# Sheet1.net
KiCad netlist of a schematic drawn in Altium Designer
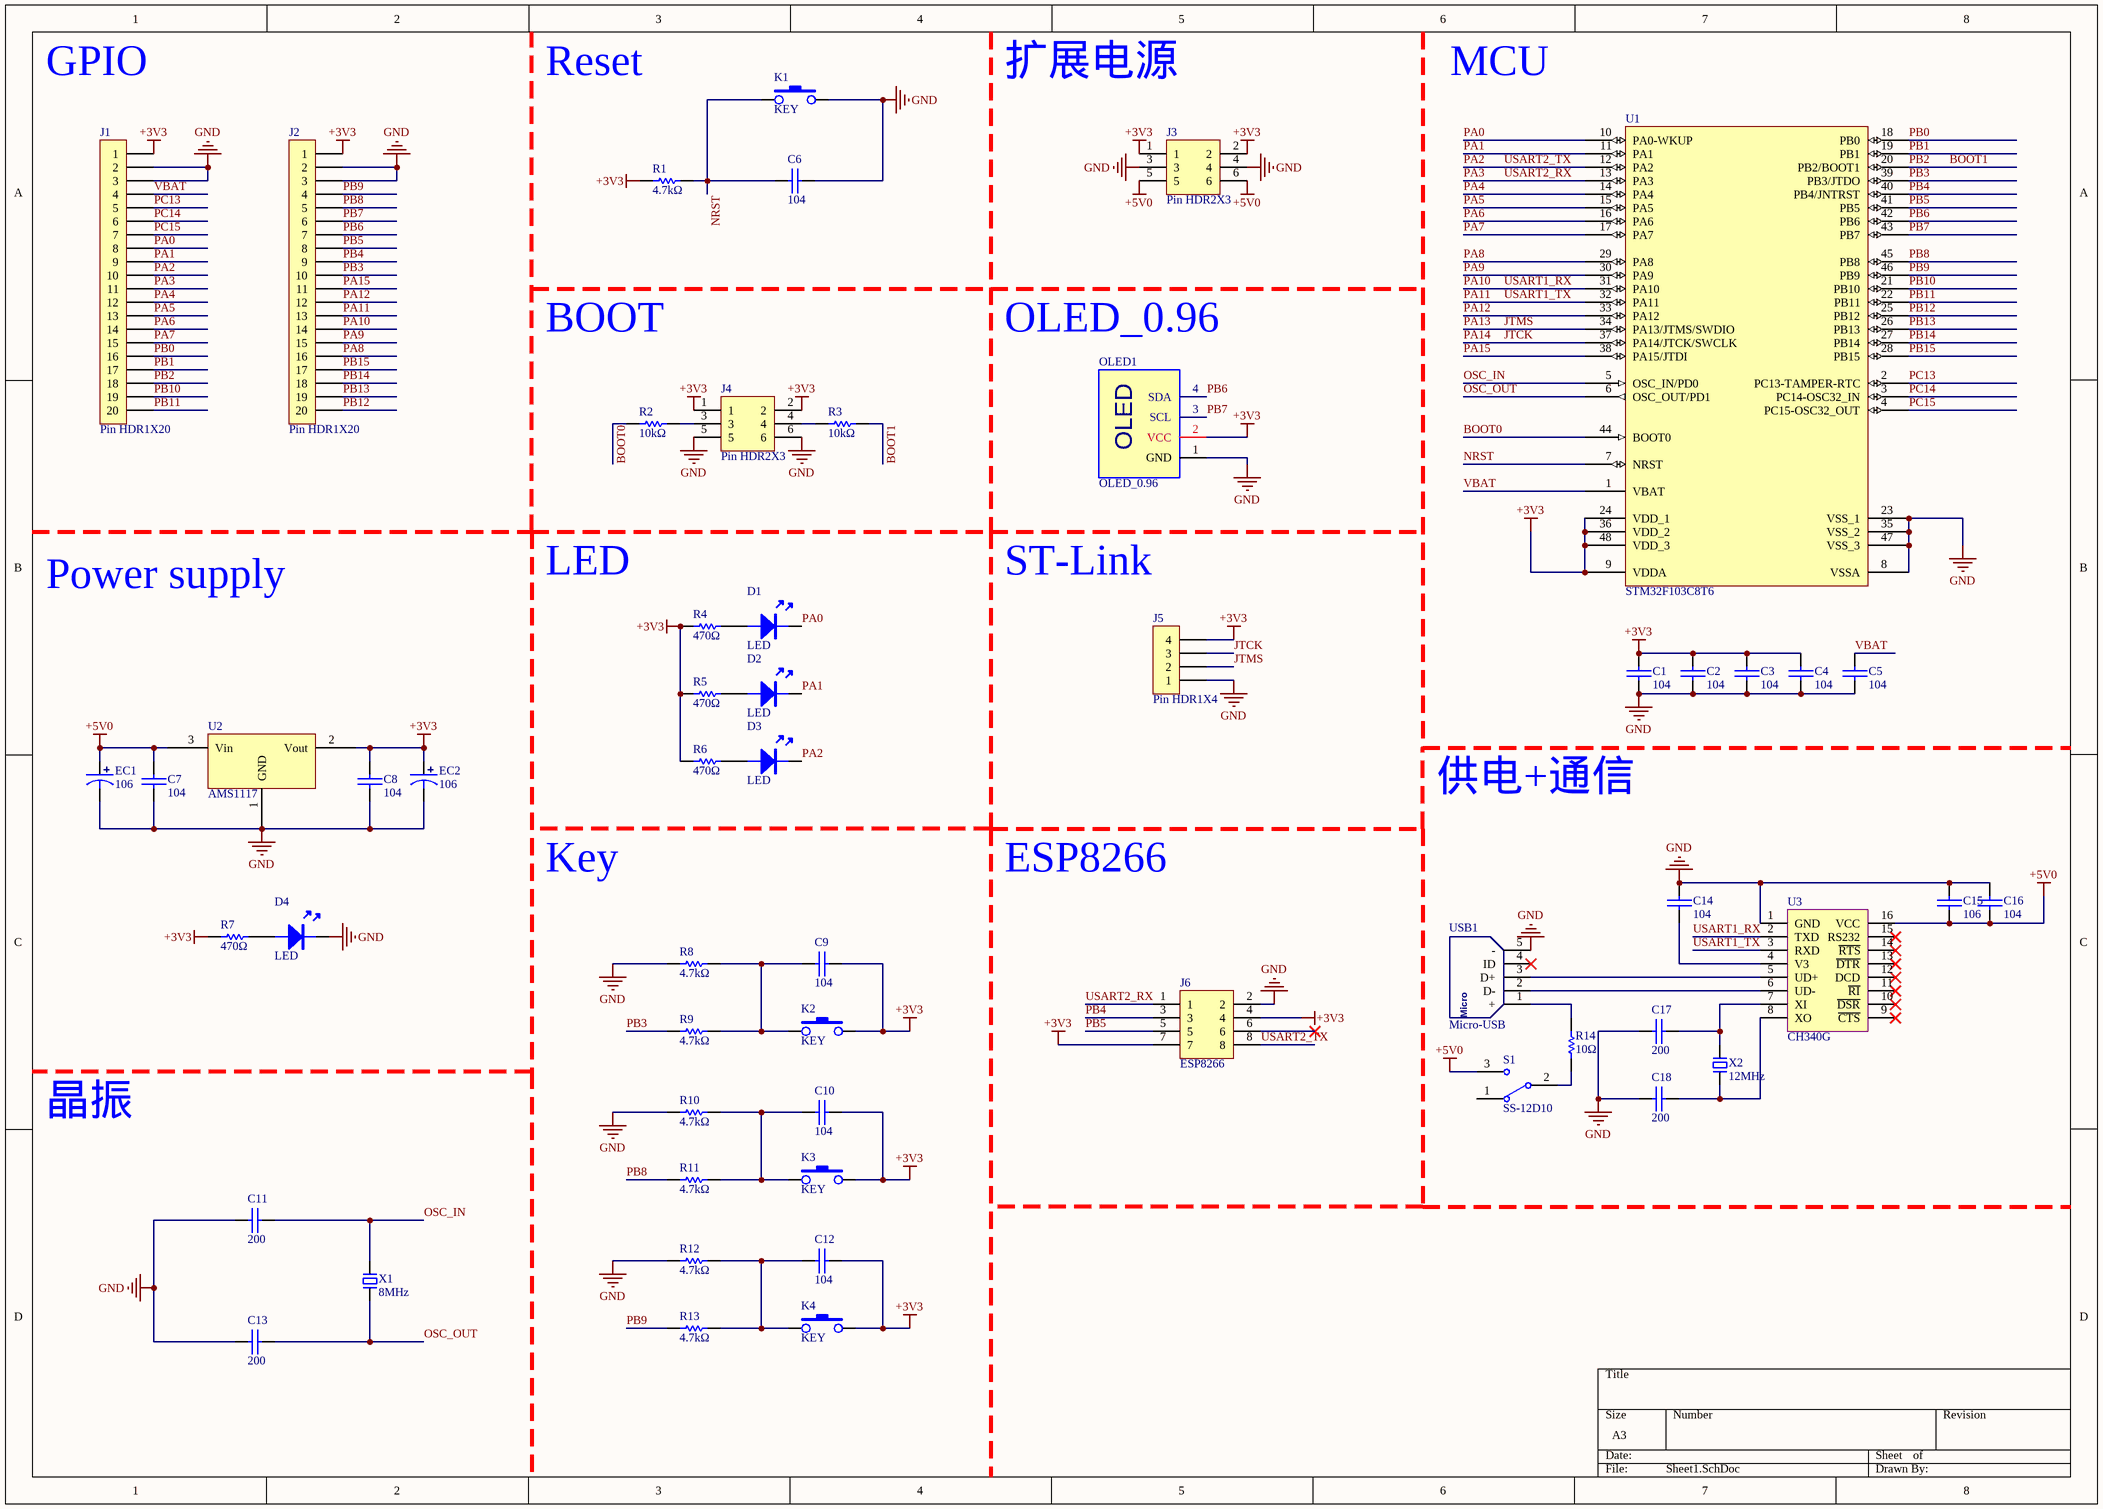
[diagram p0: Sheet1.SchDoc]

(export (version "E")
  (design (tool "Eeschema 10.0.6"))
  (components
    (comp (ref "C1")
      (value "104")
      (footprint "0805C")
      (description "无极性电容")
      (libsource (lib "电容") (part "CAP"))
    )
    (comp (ref "C2")
      (value "104")
      (footprint "0805C")
      (description "无极性电容")
      (libsource (lib "电容") (part "CAP"))
    )
    (comp (ref "C3")
      (value "104")
      (footprint "0805C")
      (description "无极性电容")
      (libsource (lib "电容") (part "CAP"))
    )
    (comp (ref "C4")
      (value "104")
      (footprint "0805C")
      (description "无极性电容")
      (libsource (lib "电容") (part "CAP"))
    )
    (comp (ref "C5")
      (value "104")
      (footprint "0805C")
      (description "无极性电容")
      (libsource (lib "电容") (part "CAP"))
    )
    (comp (ref "C6")
      (value "104")
      (footprint "0805C")
      (description "无极性电容")
      (libsource (lib "电容") (part "CAP"))
    )
    (comp (ref "C7")
      (value "104")
      (footprint "0805C")
      (description "无极性电容")
      (libsource (lib "电容") (part "CAP"))
    )
    (comp (ref "C8")
      (value "104")
      (footprint "0805C")
      (description "无极性电容")
      (libsource (lib "电容") (part "CAP"))
    )
    (comp (ref "C9")
      (value "104")
      (footprint "0805C")
      (description "无极性电容")
      (libsource (lib "电容") (part "CAP"))
    )
    (comp (ref "C10")
      (value "104")
      (footprint "0805C")
      (description "无极性电容")
      (libsource (lib "电容") (part "CAP"))
    )
    (comp (ref "C11")
      (value "200")
      (footprint "0805C")
      (description "无极性电容")
      (libsource (lib "电容") (part "CAP"))
    )
    (comp (ref "C12")
      (value "104")
      (footprint "0805C")
      (description "无极性电容")
      (libsource (lib "电容") (part "CAP"))
    )
    (comp (ref "C13")
      (value "200")
      (footprint "0805C")
      (description "无极性电容")
      (libsource (lib "电容") (part "CAP"))
    )
    (comp (ref "C14")
      (value "104")
      (footprint "0805C")
      (description "无极性电容")
      (libsource (lib "电容") (part "CAP"))
    )
    (comp (ref "C15")
      (value "106")
      (footprint "0805C")
      (description "无极性电容")
      (libsource (lib "电容") (part "CAP"))
    )
    (comp (ref "C16")
      (value "104")
      (footprint "0805C")
      (description "无极性电容")
      (libsource (lib "电容") (part "CAP"))
    )
    (comp (ref "C17")
      (value "200")
      (footprint "0805C")
      (description "无极性电容")
      (libsource (lib "电容") (part "CAP"))
    )
    (comp (ref "C18")
      (value "200")
      (footprint "0805C")
      (description "无极性电容")
      (libsource (lib "电容") (part "CAP"))
    )
    (comp (ref "D1") (value "LED") (footprint "LED-0805R") (libsource (lib "LED") (part "LED")))
    (comp (ref "D2") (value "LED") (footprint "LED-0805G") (libsource (lib "LED") (part "LED")))
    (comp (ref "D3") (value "LED") (footprint "LED-0805B") (libsource (lib "LED") (part "LED")))
    (comp (ref "D4") (value "LED") (footprint "LED-0805B") (libsource (lib "LED") (part "LED")))
    (comp (ref "EC1")
      (value "106")
      (footprint "SMD-EC4.0X4.3X5.4")
      (description "贴片电解电容")
      (libsource (lib "电容") (part "SMD_ECAP"))
    )
    (comp (ref "EC2")
      (value "106")
      (footprint "SMD-EC4.0X4.3X5.4")
      (description "贴片电解电容")
      (libsource (lib "电容") (part "SMD_ECAP"))
    )
    (comp (ref "J1")
      (value "Pin HDR1X20")
      (footprint "Pin HDR1X20/2.54mm-S")
      (libsource (lib "排针") (part "Pin HDR1X20"))
    )
    (comp (ref "J2")
      (value "Pin HDR1X20")
      (footprint "Pin HDR1X20/2.54mm-S")
      (libsource (lib "排针") (part "Pin HDR1X20"))
    )
    (comp (ref "J3")
      (value "Pin HDR2X3")
      (footprint "Pin HDR2X3/2.54mm-S")
      (libsource (lib "排针") (part "Pin HDR2X3"))
    )
    (comp (ref "J4")
      (value "Pin HDR2X3")
      (footprint "Pin HDR2X3/2.54mm-S")
      (libsource (lib "排针") (part "Pin HDR2X3"))
    )
    (comp (ref "J5")
      (value "Pin HDR1X4")
      (footprint "Pin HDR1X4/2.54mm-S")
      (libsource (lib "排针") (part "Pin HDR1X4"))
    )
    (comp (ref "J6")
      (value "ESP8266")
      (footprint "Fe-HDR2X4/2.54-S")
      (libsource (lib "排母") (part "Female HDR2X4"))
    )
    (comp (ref "K1") (value "KEY") (footprint "SMD-6X6X5") (libsource (lib "轻触开关") (part "KEY")))
    (comp (ref "K2") (value "KEY") (footprint "SMD-6X6X5") (libsource (lib "轻触开关") (part "KEY")))
    (comp (ref "K3") (value "KEY") (footprint "SMD-6X6X5") (libsource (lib "轻触开关") (part "KEY")))
    (comp (ref "K4") (value "KEY") (footprint "SMD-6X6X5") (libsource (lib "轻触开关") (part "KEY")))
    (comp (ref "OLED1")
      (value "OLED_0.96")
      (footprint "OLED_0.96")
      (libsource (lib "LCD") (part "OLED_0.96"))
    )
    (comp (ref "R1") (value "4.7kΩ") (footprint "0805R") (libsource (lib "电阻") (part "RES")))
    (comp (ref "R2") (value "10kΩ") (footprint "0805R") (libsource (lib "电阻") (part "RES")))
    (comp (ref "R3") (value "10kΩ") (footprint "0805R") (libsource (lib "电阻") (part "RES")))
    (comp (ref "R4") (value "470Ω") (footprint "0805R") (libsource (lib "电阻") (part "RES")))
    (comp (ref "R5") (value "470Ω") (footprint "0805R") (libsource (lib "电阻") (part "RES")))
    (comp (ref "R6") (value "470Ω") (footprint "0805R") (libsource (lib "电阻") (part "RES")))
    (comp (ref "R7") (value "470Ω") (footprint "0805R") (libsource (lib "电阻") (part "RES")))
    (comp (ref "R8") (value "4.7kΩ") (footprint "0805R") (libsource (lib "电阻") (part "RES")))
    (comp (ref "R9") (value "4.7kΩ") (footprint "0805R") (libsource (lib "电阻") (part "RES")))
    (comp (ref "R10") (value "4.7kΩ") (footprint "0805R") (libsource (lib "电阻") (part "RES")))
    (comp (ref "R11") (value "4.7kΩ") (footprint "0805R") (libsource (lib "电阻") (part "RES")))
    (comp (ref "R12") (value "4.7kΩ") (footprint "0805R") (libsource (lib "电阻") (part "RES")))
    (comp (ref "R13") (value "4.7kΩ") (footprint "0805R") (libsource (lib "电阻") (part "RES")))
    (comp (ref "R14") (value "10Ω") (footprint "2512R") (libsource (lib "电阻") (part "RES")))
    (comp (ref "S1") (value "SS-12D10") (footprint "SS-12D10") (libsource (lib "电源开关") (part "SS-12D10")))
    (comp (ref "U1")
      (value "STM32F103C8T6")
      (footprint "LQFP48 7X7")
      (libsource (lib "STM32系列") (part "STM32F103C8T6"))
    )
    (comp (ref "U2")
      (value "AMS1117")
      (footprint "SOT223")
      (description "三端稳压芯片")
      (libsource (lib "电源芯片") (part "AMS1117"))
    )
    (comp (ref "U3") (value "CH340G") (footprint "SOP16") (libsource (lib "通讯系列IC") (part "CH340G")))
    (comp (ref "USB1")
      (value "Micro-USB")
      (footprint "USB-MICRO_A")
      (libsource (lib "USB") (part "Micro-USB"))
    )
    (comp (ref "X1")
      (value "8MHz")
      (footprint "OSC HC-49SMD")
      (description "2脚无源脚晶振")
      (libsource (lib "晶振") (part "XTAL-2P"))
    )
    (comp (ref "X2")
      (value "12MHz")
      (footprint "OSC HC-49SMD")
      (description "2脚无源脚晶振")
      (libsource (lib "晶振") (part "XTAL-2P"))
    )
  )
  (nets
    (net (code "1") (name "+3V3") (class "Default")
      (node (ref "C1") (pin "2") (pinfunction "2_2") (pintype "passive"))
      (node (ref "C10") (pin "2") (pinfunction "2_2") (pintype "passive"))
      (node (ref "C12") (pin "2") (pinfunction "2_2") (pintype "passive"))
      (node (ref "C2") (pin "2") (pinfunction "2_2") (pintype "passive"))
      (node (ref "C3") (pin "2") (pinfunction "2_2") (pintype "passive"))
      (node (ref "C4") (pin "2") (pinfunction "2_2") (pintype "passive"))
      (node (ref "C8") (pin "2") (pinfunction "2_2") (pintype "passive"))
      (node (ref "C9") (pin "2") (pinfunction "2_2") (pintype "passive"))
      (node (ref "EC2") (pin "1") (pinfunction "1_1") (pintype "passive"))
      (node (ref "J1") (pin "1") (pinfunction "1_1") (pintype "passive"))
      (node (ref "J2") (pin "1") (pinfunction "1_1") (pintype "passive"))
      (node (ref "J3") (pin "1") (pinfunction "1_1") (pintype "passive"))
      (node (ref "J3") (pin "2") (pinfunction "2_2") (pintype "passive"))
      (node (ref "J4") (pin "1") (pinfunction "1_1") (pintype "passive"))
      (node (ref "J4") (pin "2") (pinfunction "2_2") (pintype "passive"))
      (node (ref "J5") (pin "4") (pinfunction "4_4") (pintype "passive"))
      (node (ref "J6") (pin "4") (pinfunction "4_4") (pintype "passive"))
      (node (ref "J6") (pin "7") (pinfunction "7_7") (pintype "passive"))
      (node (ref "K2") (pin "3") (pinfunction "3_3") (pintype "passive"))
      (node (ref "K3") (pin "3") (pinfunction "3_3") (pintype "passive"))
      (node (ref "K4") (pin "3") (pinfunction "3_3") (pintype "passive"))
      (node (ref "OLED1") (pin "2") (pinfunction "VCC_2") (pintype "passive"))
      (node (ref "R1") (pin "1") (pinfunction "1_1") (pintype "passive"))
      (node (ref "R4") (pin "1") (pinfunction "1_1") (pintype "passive"))
      (node (ref "R5") (pin "1") (pinfunction "1_1") (pintype "passive"))
      (node (ref "R6") (pin "1") (pinfunction "1_1") (pintype "passive"))
      (node (ref "R7") (pin "1") (pinfunction "1_1") (pintype "passive"))
      (node (ref "U1") (pin "24") (pinfunction "VDD_1_24") (pintype "power_in"))
      (node (ref "U1") (pin "36") (pinfunction "VDD_2_36") (pintype "power_in"))
      (node (ref "U1") (pin "48") (pinfunction "VDD_3_48") (pintype "power_in"))
      (node (ref "U1") (pin "9") (pinfunction "VDDA_9") (pintype "power_in"))
      (node (ref "U2") (pin "2") (pinfunction "Vout_2") (pintype "passive"))
    )
    (net (code "2") (name "+5V0") (class "Default")
      (node (ref "C15") (pin "1") (pinfunction "1_1") (pintype "passive"))
      (node (ref "C16") (pin "1") (pinfunction "1_1") (pintype "passive"))
      (node (ref "C7") (pin "1") (pinfunction "1_1") (pintype "passive"))
      (node (ref "EC1") (pin "1") (pinfunction "1_1") (pintype "passive"))
      (node (ref "J3") (pin "5") (pinfunction "5_5") (pintype "passive"))
      (node (ref "J3") (pin "6") (pinfunction "6_6") (pintype "passive"))
      (node (ref "S1") (pin "3") (pinfunction "3_3") (pintype "passive"))
      (node (ref "U2") (pin "3") (pinfunction "Vin_3") (pintype "passive"))
      (node (ref "U3") (pin "16") (pinfunction "VCC_16") (pintype "passive"))
    )
    (net (code "3") (name "/BOOT0") (class "Default")
      (node (ref "R2") (pin "1") (pinfunction "1_1") (pintype "passive"))
      (node (ref "U1") (pin "44") (pinfunction "BOOT0_44") (pintype "input"))
    )
    (net (code "4") (name "/BOOT1") (class "Default")
      (node (ref "J1") (pin "18") (pinfunction "18_18") (pintype "passive"))
      (node (ref "R3") (pin "2") (pinfunction "2_2") (pintype "passive"))
      (node (ref "U1") (pin "20") (pinfunction "PB2/BOOT1_20") (pintype "bidirectional"))
    )
    (net (code "5") (name "/JTCK") (class "Default")
      (node (ref "J5") (pin "3") (pinfunction "3_3") (pintype "passive"))
      (node (ref "U1") (pin "37") (pinfunction "PA14/JTCK/SWCLK_37") (pintype "bidirectional"))
    )
    (net (code "6") (name "/JTMS") (class "Default")
      (node (ref "J5") (pin "2") (pinfunction "2_2") (pintype "passive"))
      (node (ref "U1") (pin "34") (pinfunction "PA13/JTMS/SWDIO_34") (pintype "bidirectional"))
    )
    (net (code "7") (name "/NRST") (class "Default")
      (node (ref "C6") (pin "1") (pinfunction "1_1") (pintype "passive"))
      (node (ref "K1") (pin "1") (pinfunction "1_1") (pintype "passive"))
      (node (ref "R1") (pin "2") (pinfunction "2_2") (pintype "passive"))
      (node (ref "U1") (pin "7") (pinfunction "NRST_7") (pintype "bidirectional"))
    )
    (net (code "8") (name "/OSC_IN") (class "Default")
      (node (ref "C11") (pin "2") (pinfunction "2_2") (pintype "passive"))
      (node (ref "U1") (pin "5") (pinfunction "OSC_IN/PD0_5") (pintype "input"))
      (node (ref "X1") (pin "2") (pinfunction "2_2") (pintype "passive"))
    )
    (net (code "9") (name "/OSC_OUT") (class "Default")
      (node (ref "C13") (pin "2") (pinfunction "2_2") (pintype "passive"))
      (node (ref "U1") (pin "6") (pinfunction "OSC_OUT/PD1_6") (pintype "output"))
      (node (ref "X1") (pin "1") (pinfunction "1_1") (pintype "passive"))
    )
    (net (code "10") (name "/PA0") (class "Default")
      (node (ref "D1") (pin "K") (pinfunction "K_K") (pintype "passive"))
      (node (ref "J1") (pin "8") (pinfunction "8_8") (pintype "passive"))
      (node (ref "U1") (pin "10") (pinfunction "PA0-WKUP_10") (pintype "bidirectional"))
    )
    (net (code "11") (name "/PA1") (class "Default")
      (node (ref "D2") (pin "K") (pinfunction "K_K") (pintype "passive"))
      (node (ref "J1") (pin "9") (pinfunction "9_9") (pintype "passive"))
      (node (ref "U1") (pin "11") (pinfunction "PA1_11") (pintype "bidirectional"))
    )
    (net (code "12") (name "/PA2") (class "Default")
      (node (ref "D3") (pin "K") (pinfunction "K_K") (pintype "passive"))
      (node (ref "J1") (pin "10") (pinfunction "10_10") (pintype "passive"))
      (node (ref "J6") (pin "8") (pinfunction "8_8") (pintype "passive"))
      (node (ref "U1") (pin "12") (pinfunction "PA2_12") (pintype "bidirectional"))
    )
    (net (code "13") (name "/PA3") (class "Default")
      (node (ref "J1") (pin "11") (pinfunction "11_11") (pintype "passive"))
      (node (ref "J6") (pin "1") (pinfunction "1_1") (pintype "passive"))
      (node (ref "U1") (pin "13") (pinfunction "PA3_13") (pintype "bidirectional"))
    )
    (net (code "14") (name "/PA4") (class "Default")
      (node (ref "J1") (pin "12") (pinfunction "12_12") (pintype "passive"))
      (node (ref "U1") (pin "14") (pinfunction "PA4_14") (pintype "bidirectional"))
    )
    (net (code "15") (name "/PA5") (class "Default")
      (node (ref "J1") (pin "13") (pinfunction "13_13") (pintype "passive"))
      (node (ref "U1") (pin "15") (pinfunction "PA5_15") (pintype "bidirectional"))
    )
    (net (code "16") (name "/PA6") (class "Default")
      (node (ref "J1") (pin "14") (pinfunction "14_14") (pintype "passive"))
      (node (ref "U1") (pin "16") (pinfunction "PA6_16") (pintype "bidirectional"))
    )
    (net (code "17") (name "/PA7") (class "Default")
      (node (ref "J1") (pin "15") (pinfunction "15_15") (pintype "passive"))
      (node (ref "U1") (pin "17") (pinfunction "PA7_17") (pintype "bidirectional"))
    )
    (net (code "18") (name "/PA8") (class "Default")
      (node (ref "J2") (pin "16") (pinfunction "16_16") (pintype "passive"))
      (node (ref "U1") (pin "29") (pinfunction "PA8_29") (pintype "bidirectional"))
    )
    (net (code "19") (name "/PA9") (class "Default")
      (node (ref "J2") (pin "15") (pinfunction "15_15") (pintype "passive"))
      (node (ref "U1") (pin "30") (pinfunction "PA9_30") (pintype "bidirectional"))
    )
    (net (code "20") (name "/PA10") (class "Default")
      (node (ref "J2") (pin "14") (pinfunction "14_14") (pintype "passive"))
      (node (ref "U1") (pin "31") (pinfunction "PA10_31") (pintype "bidirectional"))
      (node (ref "U3") (pin "2") (pinfunction "TXD_2") (pintype "passive"))
    )
    (net (code "21") (name "/PA11") (class "Default")
      (node (ref "J2") (pin "13") (pinfunction "13_13") (pintype "passive"))
      (node (ref "U1") (pin "32") (pinfunction "PA11_32") (pintype "bidirectional"))
      (node (ref "U3") (pin "3") (pinfunction "RXD_3") (pintype "passive"))
    )
    (net (code "22") (name "/PA12") (class "Default")
      (node (ref "J2") (pin "12") (pinfunction "12_12") (pintype "passive"))
      (node (ref "U1") (pin "33") (pinfunction "PA12_33") (pintype "bidirectional"))
    )
    (net (code "23") (name "/PA15") (class "Default")
      (node (ref "J2") (pin "11") (pinfunction "11_11") (pintype "passive"))
      (node (ref "U1") (pin "38") (pinfunction "PA15/JTDI_38") (pintype "bidirectional"))
    )
    (net (code "24") (name "/PB0") (class "Default")
      (node (ref "J1") (pin "16") (pinfunction "16_16") (pintype "passive"))
      (node (ref "U1") (pin "18") (pinfunction "PB0_18") (pintype "bidirectional"))
    )
    (net (code "25") (name "/PB1") (class "Default")
      (node (ref "J1") (pin "17") (pinfunction "17_17") (pintype "passive"))
      (node (ref "U1") (pin "19") (pinfunction "PB1_19") (pintype "bidirectional"))
    )
    (net (code "26") (name "/PB3") (class "Default")
      (node (ref "J2") (pin "10") (pinfunction "10_10") (pintype "passive"))
      (node (ref "R9") (pin "1") (pinfunction "1_1") (pintype "passive"))
      (node (ref "U1") (pin "39") (pinfunction "PB3/JTDO_39") (pintype "bidirectional"))
    )
    (net (code "27") (name "/PB4") (class "Default")
      (node (ref "J2") (pin "9") (pinfunction "9_9") (pintype "passive"))
      (node (ref "J6") (pin "3") (pinfunction "3_3") (pintype "passive"))
      (node (ref "U1") (pin "40") (pinfunction "PB4/JNTRST_40") (pintype "bidirectional"))
    )
    (net (code "28") (name "/PB5") (class "Default")
      (node (ref "J2") (pin "8") (pinfunction "8_8") (pintype "passive"))
      (node (ref "J6") (pin "5") (pinfunction "5_5") (pintype "passive"))
      (node (ref "U1") (pin "41") (pinfunction "PB5_41") (pintype "bidirectional"))
    )
    (net (code "29") (name "/PB6") (class "Default")
      (node (ref "J2") (pin "7") (pinfunction "7_7") (pintype "passive"))
      (node (ref "OLED1") (pin "4") (pinfunction "SDA_4") (pintype "passive"))
      (node (ref "U1") (pin "42") (pinfunction "PB6_42") (pintype "bidirectional"))
    )
    (net (code "30") (name "/PB7") (class "Default")
      (node (ref "J2") (pin "6") (pinfunction "6_6") (pintype "passive"))
      (node (ref "OLED1") (pin "3") (pinfunction "SCL_3") (pintype "passive"))
      (node (ref "U1") (pin "43") (pinfunction "PB7_43") (pintype "bidirectional"))
    )
    (net (code "31") (name "/PB8") (class "Default")
      (node (ref "J2") (pin "5") (pinfunction "5_5") (pintype "passive"))
      (node (ref "R11") (pin "1") (pinfunction "1_1") (pintype "passive"))
      (node (ref "U1") (pin "45") (pinfunction "PB8_45") (pintype "bidirectional"))
    )
    (net (code "32") (name "/PB9") (class "Default")
      (node (ref "J2") (pin "4") (pinfunction "4_4") (pintype "passive"))
      (node (ref "R13") (pin "1") (pinfunction "1_1") (pintype "passive"))
      (node (ref "U1") (pin "46") (pinfunction "PB9_46") (pintype "bidirectional"))
    )
    (net (code "33") (name "/PB10") (class "Default")
      (node (ref "J1") (pin "19") (pinfunction "19_19") (pintype "passive"))
      (node (ref "U1") (pin "21") (pinfunction "PB10_21") (pintype "bidirectional"))
    )
    (net (code "34") (name "/PB11") (class "Default")
      (node (ref "J1") (pin "20") (pinfunction "20_20") (pintype "passive"))
      (node (ref "U1") (pin "22") (pinfunction "PB11_22") (pintype "bidirectional"))
    )
    (net (code "35") (name "/PB12") (class "Default")
      (node (ref "J2") (pin "20") (pinfunction "20_20") (pintype "passive"))
      (node (ref "U1") (pin "25") (pinfunction "PB12_25") (pintype "bidirectional"))
    )
    (net (code "36") (name "/PB13") (class "Default")
      (node (ref "J2") (pin "19") (pinfunction "19_19") (pintype "passive"))
      (node (ref "U1") (pin "26") (pinfunction "PB13_26") (pintype "bidirectional"))
    )
    (net (code "37") (name "/PB14") (class "Default")
      (node (ref "J2") (pin "18") (pinfunction "18_18") (pintype "passive"))
      (node (ref "U1") (pin "27") (pinfunction "PB14_27") (pintype "bidirectional"))
    )
    (net (code "38") (name "/PB15") (class "Default")
      (node (ref "J2") (pin "17") (pinfunction "17_17") (pintype "passive"))
      (node (ref "U1") (pin "28") (pinfunction "PB15_28") (pintype "bidirectional"))
    )
    (net (code "39") (name "/PC13") (class "Default")
      (node (ref "J1") (pin "5") (pinfunction "5_5") (pintype "passive"))
      (node (ref "U1") (pin "2") (pinfunction "PC13-TAMPER-RTC_2") (pintype "bidirectional"))
    )
    (net (code "40") (name "/PC14") (class "Default")
      (node (ref "J1") (pin "6") (pinfunction "6_6") (pintype "passive"))
      (node (ref "U1") (pin "3") (pinfunction "PC14-OSC32_IN_3") (pintype "bidirectional"))
    )
    (net (code "41") (name "/PC15") (class "Default")
      (node (ref "J1") (pin "7") (pinfunction "7_7") (pintype "passive"))
      (node (ref "U1") (pin "4") (pinfunction "PC15-OSC32_OUT_4") (pintype "bidirectional"))
    )
    (net (code "42") (name "/VBAT") (class "Default")
      (node (ref "C5") (pin "2") (pinfunction "2_2") (pintype "passive"))
      (node (ref "J1") (pin "4") (pinfunction "4_4") (pintype "passive"))
      (node (ref "U1") (pin "1") (pinfunction "VBAT_1") (pintype "power_in"))
    )
    (net (code "43") (name "GND") (class "Default")
      (node (ref "C1") (pin "1") (pinfunction "1_1") (pintype "passive"))
      (node (ref "C11") (pin "1") (pinfunction "1_1") (pintype "passive"))
      (node (ref "C13") (pin "1") (pinfunction "1_1") (pintype "passive"))
      (node (ref "C14") (pin "2") (pinfunction "2_2") (pintype "passive"))
      (node (ref "C15") (pin "2") (pinfunction "2_2") (pintype "passive"))
      (node (ref "C16") (pin "2") (pinfunction "2_2") (pintype "passive"))
      (node (ref "C17") (pin "1") (pinfunction "1_1") (pintype "passive"))
      (node (ref "C18") (pin "1") (pinfunction "1_1") (pintype "passive"))
      (node (ref "C2") (pin "1") (pinfunction "1_1") (pintype "passive"))
      (node (ref "C3") (pin "1") (pinfunction "1_1") (pintype "passive"))
      (node (ref "C4") (pin "1") (pinfunction "1_1") (pintype "passive"))
      (node (ref "C5") (pin "1") (pinfunction "1_1") (pintype "passive"))
      (node (ref "C6") (pin "2") (pinfunction "2_2") (pintype "passive"))
      (node (ref "C7") (pin "2") (pinfunction "2_2") (pintype "passive"))
      (node (ref "C8") (pin "1") (pinfunction "1_1") (pintype "passive"))
      (node (ref "D4") (pin "K") (pinfunction "K_K") (pintype "passive"))
      (node (ref "EC1") (pin "2") (pinfunction "2_2") (pintype "passive"))
      (node (ref "EC2") (pin "2") (pinfunction "2_2") (pintype "passive"))
      (node (ref "J1") (pin "2") (pinfunction "2_2") (pintype "passive"))
      (node (ref "J1") (pin "3") (pinfunction "3_3") (pintype "passive"))
      (node (ref "J2") (pin "2") (pinfunction "2_2") (pintype "passive"))
      (node (ref "J2") (pin "3") (pinfunction "3_3") (pintype "passive"))
      (node (ref "J3") (pin "3") (pinfunction "3_3") (pintype "passive"))
      (node (ref "J3") (pin "4") (pinfunction "4_4") (pintype "passive"))
      (node (ref "J4") (pin "5") (pinfunction "5_5") (pintype "passive"))
      (node (ref "J4") (pin "6") (pinfunction "6_6") (pintype "passive"))
      (node (ref "J5") (pin "1") (pinfunction "1_1") (pintype "passive"))
      (node (ref "J6") (pin "2") (pinfunction "2_2") (pintype "passive"))
      (node (ref "K1") (pin "3") (pinfunction "3_3") (pintype "passive"))
      (node (ref "OLED1") (pin "1") (pinfunction "GND_1") (pintype "passive"))
      (node (ref "R10") (pin "1") (pinfunction "1_1") (pintype "passive"))
      (node (ref "R12") (pin "1") (pinfunction "1_1") (pintype "passive"))
      (node (ref "R8") (pin "1") (pinfunction "1_1") (pintype "passive"))
      (node (ref "U1") (pin "23") (pinfunction "VSS_1_23") (pintype "power_in"))
      (node (ref "U1") (pin "35") (pinfunction "VSS_2_35") (pintype "power_in"))
      (node (ref "U1") (pin "47") (pinfunction "VSS_3_47") (pintype "power_in"))
      (node (ref "U1") (pin "8") (pinfunction "VSSA_8") (pintype "power_in"))
      (node (ref "U2") (pin "1") (pinfunction "GND_1") (pintype "passive"))
      (node (ref "U3") (pin "1") (pinfunction "GND_1") (pintype "passive"))
      (node (ref "USB1") (pin "5") (pinfunction "-_5") (pintype "passive"))
    )
    (net (code "44") (name "Net-(C9-Pad1)") (class "Default")
      (node (ref "C9") (pin "1") (pinfunction "1_1") (pintype "passive"))
      (node (ref "K2") (pin "1") (pinfunction "1_1") (pintype "passive"))
      (node (ref "R8") (pin "2") (pinfunction "2_2") (pintype "passive"))
      (node (ref "R9") (pin "2") (pinfunction "2_2") (pintype "passive"))
    )
    (net (code "45") (name "Net-(C10-Pad1)") (class "Default")
      (node (ref "C10") (pin "1") (pinfunction "1_1") (pintype "passive"))
      (node (ref "K3") (pin "1") (pinfunction "1_1") (pintype "passive"))
      (node (ref "R10") (pin "2") (pinfunction "2_2") (pintype "passive"))
      (node (ref "R11") (pin "2") (pinfunction "2_2") (pintype "passive"))
    )
    (net (code "46") (name "Net-(C12-Pad1)") (class "Default")
      (node (ref "C12") (pin "1") (pinfunction "1_1") (pintype "passive"))
      (node (ref "K4") (pin "1") (pinfunction "1_1") (pintype "passive"))
      (node (ref "R12") (pin "2") (pinfunction "2_2") (pintype "passive"))
      (node (ref "R13") (pin "2") (pinfunction "2_2") (pintype "passive"))
    )
    (net (code "47") (name "Net-(D1-PadA)") (class "Default")
      (node (ref "D1") (pin "A") (pinfunction "A_A") (pintype "passive"))
      (node (ref "R4") (pin "2") (pinfunction "2_2") (pintype "passive"))
    )
    (net (code "48") (name "Net-(D2-PadA)") (class "Default")
      (node (ref "D2") (pin "A") (pinfunction "A_A") (pintype "passive"))
      (node (ref "R5") (pin "2") (pinfunction "2_2") (pintype "passive"))
    )
    (net (code "49") (name "Net-(D3-PadA)") (class "Default")
      (node (ref "D3") (pin "A") (pinfunction "A_A") (pintype "passive"))
      (node (ref "R6") (pin "2") (pinfunction "2_2") (pintype "passive"))
    )
    (net (code "50") (name "Net-(D4-PadA)") (class "Default")
      (node (ref "D4") (pin "A") (pinfunction "A_A") (pintype "passive"))
      (node (ref "R7") (pin "2") (pinfunction "2_2") (pintype "passive"))
    )
    (net (code "51") (name "Net-(J4-Pad3)") (class "Default")
      (node (ref "J4") (pin "3") (pinfunction "3_3") (pintype "passive"))
      (node (ref "R2") (pin "2") (pinfunction "2_2") (pintype "passive"))
    )
    (net (code "52") (name "Net-(J4-Pad4)") (class "Default")
      (node (ref "J4") (pin "4") (pinfunction "4_4") (pintype "passive"))
      (node (ref "R3") (pin "1") (pinfunction "1_1") (pintype "passive"))
    )
    (net (code "53") (name "Net-(R14-Pad1)") (class "Default")
      (node (ref "R14") (pin "1") (pinfunction "1_1") (pintype "passive"))
      (node (ref "S1") (pin "2") (pinfunction "2_2") (pintype "passive"))
    )
    (net (code "54") (name "Net-(U3-UD+)") (class "Default")
      (node (ref "U3") (pin "5") (pinfunction "UD+_5") (pintype "passive"))
      (node (ref "USB1") (pin "3") (pinfunction "D+_3") (pintype "passive"))
    )
    (net (code "55") (name "Net-(U3-UD-)") (class "Default")
      (node (ref "U3") (pin "6") (pinfunction "UD-_6") (pintype "passive"))
      (node (ref "USB1") (pin "2") (pinfunction "D-_2") (pintype "passive"))
    )
    (net (code "56") (name "Net-(U3-V3)") (class "Default")
      (node (ref "C14") (pin "1") (pinfunction "1_1") (pintype "passive"))
      (node (ref "U3") (pin "4") (pinfunction "V3_4") (pintype "passive"))
    )
    (net (code "57") (name "Net-(U3-XI)") (class "Default")
      (node (ref "C17") (pin "2") (pinfunction "2_2") (pintype "passive"))
      (node (ref "U3") (pin "7") (pinfunction "XI_7") (pintype "passive"))
      (node (ref "X2") (pin "2") (pinfunction "2_2") (pintype "passive"))
    )
    (net (code "58") (name "Net-(U3-XO)") (class "Default")
      (node (ref "C18") (pin "2") (pinfunction "2_2") (pintype "passive"))
      (node (ref "U3") (pin "8") (pinfunction "XO_8") (pintype "passive"))
      (node (ref "X2") (pin "1") (pinfunction "1_1") (pintype "passive"))
    )
    (net (code "59") (name "Net-(USB1-+)") (class "Default")
      (node (ref "R14") (pin "2") (pinfunction "2_2") (pintype "passive"))
      (node (ref "USB1") (pin "1") (pinfunction "+_1") (pintype "passive"))
    )
    (net (code "60") (name "unconnected-(J6-Pad6)") (class "Default")
      (node (ref "J6") (pin "6") (pinfunction "6_6") (pintype "passive+no_connect"))
    )
    (net (code "61") (name "unconnected-(S1-Pad1)") (class "Default")
      (node (ref "S1") (pin "1") (pinfunction "1_1") (pintype "passive"))
    )
    (net (code "62") (name "unconnected-(U3-DCD-Pad12)") (class "Default")
      (node (ref "U3") (pin "12") (pinfunction "DCD_12") (pintype "passive+no_connect"))
    )
    (net (code "63") (name "unconnected-(U3-RS232-Pad15)") (class "Default")
      (node (ref "U3") (pin "15") (pinfunction "RS232_15") (pintype "passive+no_connect"))
    )
    (net (code "64") (name "unconnected-(U3-~{CTS}-Pad9)") (class "Default")
      (node (ref "U3") (pin "9") (pinfunction "~{CTS}_9") (pintype "passive+no_connect"))
    )
    (net (code "65") (name "unconnected-(U3-~{DSR}-Pad10)") (class "Default")
      (node (ref "U3") (pin "10") (pinfunction "~{DSR}_10") (pintype "passive+no_connect"))
    )
    (net (code "66") (name "unconnected-(U3-~{DTR}-Pad13)") (class "Default")
      (node (ref "U3") (pin "13") (pinfunction "~{DTR}_13") (pintype "passive+no_connect"))
    )
    (net (code "67") (name "unconnected-(U3-~{RI}-Pad11)") (class "Default")
      (node (ref "U3") (pin "11") (pinfunction "~{RI}_11") (pintype "passive+no_connect"))
    )
    (net (code "68") (name "unconnected-(U3-~{RTS}-Pad14)") (class "Default")
      (node (ref "U3") (pin "14") (pinfunction "~{RTS}_14") (pintype "passive+no_connect"))
    )
    (net (code "69") (name "unconnected-(USB1-ID-Pad4)") (class "Default")
      (node (ref "USB1") (pin "4") (pinfunction "ID_4") (pintype "passive+no_connect"))
    )
  )
)
